# heat_control.net
KiCad netlist of a schematic drawn in Altium Designer
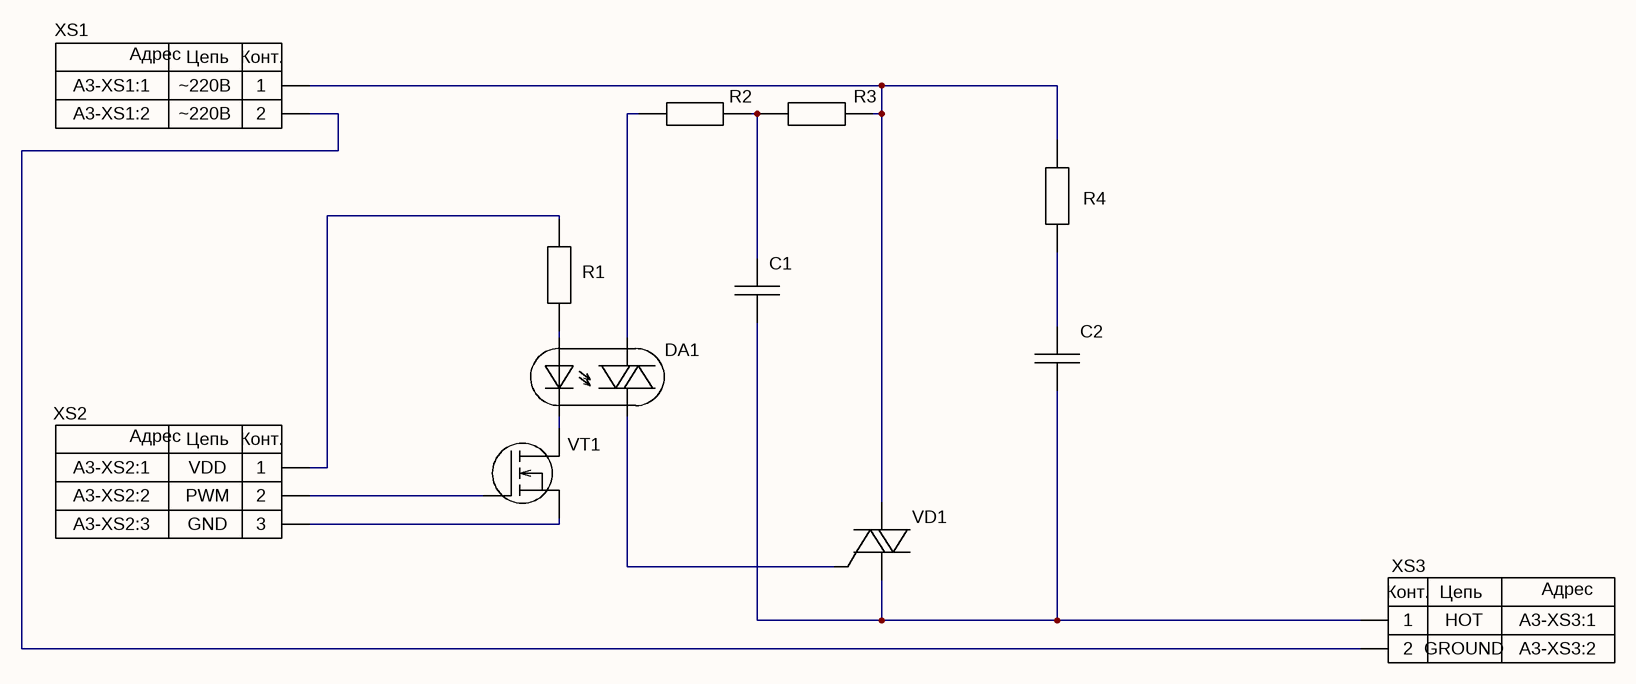
[diagram p0: heat_control.SchDoc]

(export (version "E")
  (design (tool "Eeschema 10.0.6"))
  (components
    (comp (ref "C1") (value "10 нФ") (footprint "B32652") (libsource (lib "elems") (part "C_const")))
    (comp (ref "C2") (value "10 нФ") (footprint "B32652") (libsource (lib "elems") (part "C_const")))
    (comp (ref "DA1")
      (value "MOC3020M")
      (footprint "DIP762W48P254L889H508Q6")
      (libsource (lib "elems") (part "opto_triak"))
    )
    (comp (ref "R1") (value "Res") (libsource (lib "elems") (part "Res")))
    (comp (ref "R2") (value "Res") (libsource (lib "elems") (part "Res")))
    (comp (ref "R3") (value "Res") (libsource (lib "elems") (part "Res")))
    (comp (ref "R4") (value "Res") (libsource (lib "elems") (part "Res")))
    (comp (ref "VD1") (value "BT137-600E") (footprint "TO220") (libsource (lib "elems") (part "triac")))
    (comp (ref "VT1") (value "FDV303N") (footprint "SOT23") (libsource (lib "elems") (part "n-mosfet")))
    (comp (ref "XS1")
      (value "XS?")
      (footprint "CON: WF-02")
      (fields
        (field (name "CIRCUIT2") "~220В")
        (field (name "CIRCUIT1") "~220В")
        (field (name "=ADDRESS2") "A3-XS1:2")
        (field (name "=ADDRESS1") "A3-XS1:1")
      )
      (libsource (lib "elems") (part "X2"))
    )
    (comp (ref "XS2")
      (value "XS?")
      (footprint "CON: WF-03")
      (fields
        (field (name "CIRCUIT1") "VDD")
        (field (name "CIRCUIT2") "PWM")
        (field (name "CIRCUIT3") "GND")
        (field (name "=ADDRESS1") "A3-XS2:1")
        (field (name "=ADDRESS2") "A3-XS2:2")
        (field (name "=ADDRESS3") "A3-XS2:3")
      )
      (libsource (lib "elems") (part "X3"))
    )
    (comp (ref "XS3")
      (value "X2")
      (footprint "CON: WF-02")
      (fields
        (field (name "CIRCUIT2") "GROUND")
        (field (name "CIRCUIT1") "HOT")
        (field (name "=ADDRESS2") "A3-XS3:2")
        (field (name "=ADDRESS1") "A3-XS3:1")
      )
      (libsource (lib "elems") (part "X2"))
    )
  )
  (nets
    (net (code "1") (name "Net-(C1-Pad1)") (class "Default")
      (node (ref "C1") (pin "1") (pinfunction "1_1") (pintype "passive"))
      (node (ref "C2") (pin "1") (pinfunction "1_1") (pintype "passive"))
      (node (ref "VD1") (pin "1") (pinfunction "1_1") (pintype "passive"))
      (node (ref "XS3") (pin "1") (pinfunction "1_1") (pintype "passive"))
    )
    (net (code "2") (name "Net-(DA1-Pad1)") (class "Default")
      (node (ref "DA1") (pin "1") (pinfunction "1_1") (pintype "passive"))
      (node (ref "R1") (pin "1") (pinfunction "1_1") (pintype "passive"))
    )
    (net (code "3") (name "Net-(DA1-Pad2)") (class "Default")
      (node (ref "DA1") (pin "2") (pinfunction "2_2") (pintype "passive"))
      (node (ref "VT1") (pin "2") (pinfunction "2_2") (pintype "passive"))
    )
    (net (code "4") (name "Net-(DA1-Pad3)") (class "Default")
      (node (ref "DA1") (pin "3") (pinfunction "3_3") (pintype "passive"))
      (node (ref "R2") (pin "1") (pinfunction "1_1") (pintype "passive"))
    )
    (net (code "5") (name "Net-(DA1-Pad4)") (class "Default")
      (node (ref "DA1") (pin "4") (pinfunction "4_4") (pintype "passive"))
      (node (ref "VD1") (pin "3") (pinfunction "3_3") (pintype "passive"))
    )
    (net (code "6") (name "Net-(R1-6)") (class "Default")
      (node (ref "R1") (pin "2") (pinfunction "6_2") (pintype "passive"))
      (node (ref "XS2") (pin "1") (pinfunction "1_1") (pintype "passive"))
    )
    (net (code "7") (name "Net-(R2-6)") (class "Default")
      (node (ref "C1") (pin "2") (pinfunction "2_2") (pintype "passive"))
      (node (ref "R2") (pin "2") (pinfunction "6_2") (pintype "passive"))
      (node (ref "R3") (pin "1") (pinfunction "1_1") (pintype "passive"))
    )
    (net (code "8") (name "Net-(R3-6)") (class "Default")
      (node (ref "R3") (pin "2") (pinfunction "6_2") (pintype "passive"))
      (node (ref "R4") (pin "1") (pinfunction "1_1") (pintype "passive"))
      (node (ref "VD1") (pin "2") (pinfunction "2_2") (pintype "passive"))
      (node (ref "XS1") (pin "1") (pinfunction "1_1") (pintype "passive"))
    )
    (net (code "9") (name "Net-(R4-6)") (class "Default")
      (node (ref "C2") (pin "2") (pinfunction "2_2") (pintype "passive"))
      (node (ref "R4") (pin "2") (pinfunction "6_2") (pintype "passive"))
    )
    (net (code "10") (name "Net-(VT1-Pad1)") (class "Default")
      (node (ref "VT1") (pin "1") (pinfunction "1_1") (pintype "passive"))
      (node (ref "XS2") (pin "2") (pinfunction "2_2") (pintype "passive"))
    )
    (net (code "11") (name "Net-(VT1-Pad3)") (class "Default")
      (node (ref "VT1") (pin "3") (pinfunction "3_3") (pintype "passive"))
      (node (ref "XS2") (pin "3") (pinfunction "3_3") (pintype "passive"))
    )
    (net (code "12") (name "Net-(XS1-Pad2)") (class "Default")
      (node (ref "XS1") (pin "2") (pinfunction "2_2") (pintype "passive"))
      (node (ref "XS3") (pin "2") (pinfunction "2_2") (pintype "passive"))
    )
  )
)
